# Power_Supply.net
KiCad netlist of a schematic drawn in Altium Designer
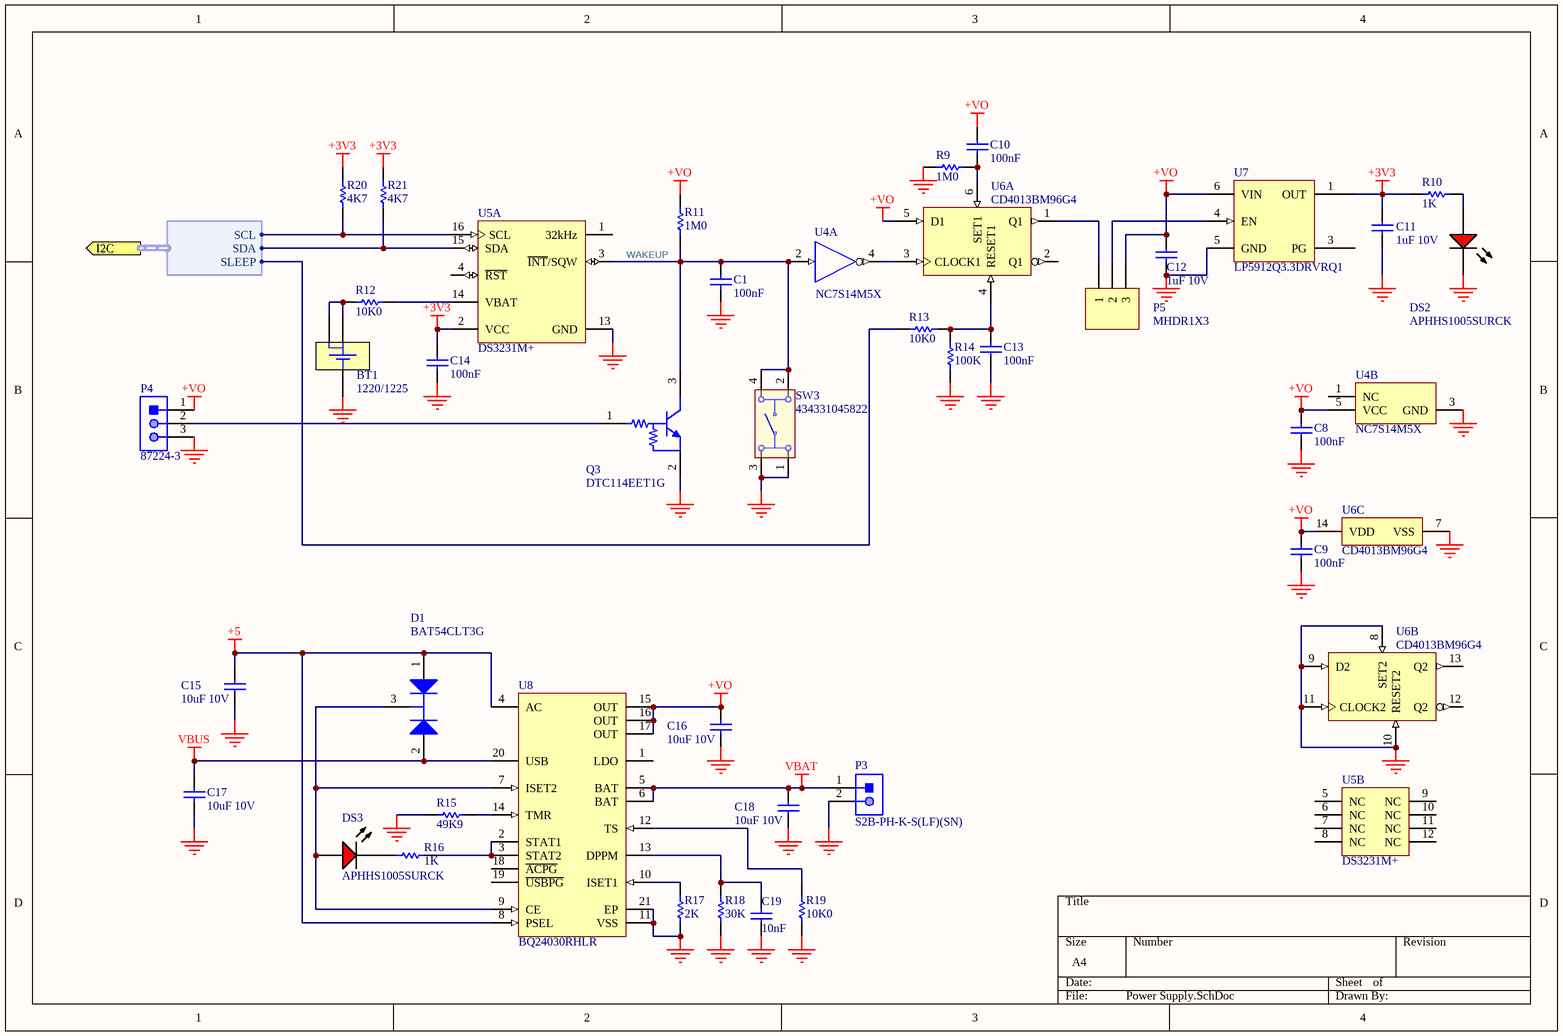
[diagram p0: Power Supply.SchDoc]

(export (version "E")
  (design (tool "Eeschema 10.0.6"))
  (components
    (comp (ref "BT1")
      (value "1220/1225")
      (footprint "KEYSTONE 3000")
      (description "Keystone 3000")
      (libsource (lib "Pathfinder") (part "3000"))
    )
    (comp (ref "C1")
      (value "100nF")
      (footprint "CAPC0402(1005)60_L")
      (description "CAP 100nF 50V ±10% 0402 (1005 Metric) Thickness 0.6mm SMD")
      (fields (field (name "TOLERANCE") "Â±10%"))
      (libsource (lib "Altium Content Vault") (part "CAP"))
    )
    (comp (ref "C8")
      (value "100nF")
      (footprint "CAPC0402(1005)60_L")
      (description "CAP 100nF 50V ±10% 0402 (1005 Metric) Thickness 0.6mm SMD")
      (fields (field (name "TOLERANCE") "Â±10%"))
      (libsource (lib "Altium Content Vault") (part "CAP"))
    )
    (comp (ref "C9")
      (value "100nF")
      (footprint "CAPC0402(1005)60_N")
      (description "CAP 100nF 50V ±10% 0402 (1005 Metric) Thickness 0.6mm SMD")
      (fields (field (name "TOLERANCE") "Â±10%"))
      (libsource (lib "Altium Content Vault") (part "CAP"))
    )
    (comp (ref "C10")
      (value "100nF")
      (footprint "CAPC0402(1005)60_L")
      (description "CAP 100nF 50V ±10% 0402 (1005 Metric) Thickness 0.6mm SMD")
      (fields (field (name "TOLERANCE") "Â±10%"))
      (libsource (lib "Altium Content Vault") (part "CAP"))
    )
    (comp (ref "C11")
      (value "1uF 10V")
      (footprint "CAPC0402(1005)60_L")
      (description "CAP 1uF 10V ±10% 0402 (1005 Metric) Thickness 0.6mm SMD")
      (fields (field (name "TOLERANCE") "Â±10%"))
      (libsource (lib "Altium Content Vault") (part "CAP"))
    )
    (comp (ref "C12")
      (value "1uF 10V")
      (footprint "CAPC0402(1005)60_L")
      (description "CAP 1uF 10V ±10% 0402 (1005 Metric) Thickness 0.6mm SMD")
      (fields (field (name "TOLERANCE") "Â±10%"))
      (libsource (lib "Altium Content Vault") (part "CAP"))
    )
    (comp (ref "C13")
      (value "100nF")
      (footprint "CAPC0402(1005)60_L")
      (description "CAP 100nF 50V ±10% 0402 (1005 Metric) Thickness 0.6mm SMD")
      (fields (field (name "TOLERANCE") "Â±10%"))
      (libsource (lib "Altium Content Vault") (part "CAP"))
    )
    (comp (ref "C14")
      (value "100nF")
      (footprint "CAPC0402(1005)60_L")
      (description "CAP 100nF 50V ±10% 0402 (1005 Metric) Thickness 0.6mm SMD")
      (fields (field (name "TOLERANCE") "Â±10%"))
      (libsource (lib "Altium Content Vault") (part "CAP"))
    )
    (comp (ref "C15")
      (value "10uF 10V")
      (footprint "CAPC0603(1608)100_L")
      (description "CAP 10uF 10V ±20% 0603 (1608 Metric) Thickness 1mm SMD")
      (fields (field (name "TOLERANCE") "Â±20%"))
      (libsource (lib "Altium Content Vault") (part "CAP"))
    )
    (comp (ref "C16")
      (value "10uF 10V")
      (footprint "CAPC0603(1608)100_L")
      (description "CAP 10uF 10V ±20% 0603 (1608 Metric) Thickness 1mm SMD")
      (fields (field (name "TOLERANCE") "Â±20%"))
      (libsource (lib "Altium Content Vault") (part "CAP"))
    )
    (comp (ref "C17")
      (value "10uF 10V")
      (footprint "CAPC0603(1608)100_L")
      (description "CAP 10uF 10V ±20% 0603 (1608 Metric) Thickness 1mm SMD")
      (fields (field (name "TOLERANCE") "Â±20%"))
      (libsource (lib "Altium Content Vault") (part "CAP"))
    )
    (comp (ref "C18")
      (value "10uF 10V")
      (footprint "CAPC0603(1608)100_L")
      (description "CAP 10uF 10V ±20% 0603 (1608 Metric) Thickness 1mm SMD")
      (fields (field (name "TOLERANCE") "Â±20%"))
      (libsource (lib "Altium Content Vault") (part "CAP"))
    )
    (comp (ref "C19")
      (value "10nF")
      (footprint "CAPC0402(1005)60_L")
      (description "CAP 10nF 50V ±10% 0402 (1005 Metric) Thickness 0.6mm SMD")
      (fields (field (name "TOLERANCE") "Â±10%"))
      (libsource (lib "Altium Content Vault") (part "CAP"))
    )
    (comp (ref "D1")
      (value "BAT54CLT3G")
      (footprint "ONSC-SOT-23-3-318-08_V")
      (description "Dual Common Cathode Schottky Barrier Diodes, 3-Pin SOT-23, Pb-Free, Tape and Reel")
      (fields (field (name "MANUFACTURER") "On Semiconductor"))
      (libsource (lib "Altium Content Vault") (part "ONSC-D-A1A2K3-3"))
    )
    (comp (ref "DS2")
      (value "APHHS1005SURCK")
      (footprint "KING-0402_V")
      (fields (field (name "MANUFACTURER") "Kingbright"))
      (libsource (lib "Altium Content Vault") (part "LED-RED-AK-2"))
    )
    (comp (ref "DS3")
      (value "APHHS1005SURCK")
      (footprint "KING-0402_V")
      (fields (field (name "MANUFACTURER") "Kingbright"))
      (libsource (lib "Altium Content Vault") (part "LED-RED-AK-2"))
    )
    (comp (ref "P3")
      (value "S2B-PH-K-S(LF)(SN)")
      (footprint "JST-S2B-PH-K-S_V")
      (fields (field (name "TOLERANCE") "20%"))
      (libsource (lib "Altium Content Vault") (part "CN-1P-M-R2"))
    )
    (comp (ref "P4")
      (value "87224-3")
      (footprint "TECO-87224-3_V")
      (fields (field (name "MANUFACTURER") "TE Connectivity"))
      (libsource (lib "Altium Content Vault") (part "CN-1P-M-R3"))
    )
    (comp (ref "P5")
      (value "MHDR1X3")
      (footprint "MHDR1X3")
      (description "Header, 3-Pin")
      (fields (field (name "PUBLISHER") "Altium Limited"))
      (libsource (lib "Miscellaneous Connectors") (part "MHDR1X3"))
    )
    (comp (ref "Q3")
      (value "DTC114EET1G")
      (footprint "ONSC-SC-75-3-463-01_V")
      (fields (field (name "MANUFACTURER") "On Semiconductor"))
      (libsource (lib "Altium Content Vault") (part "ONSC-BRT-NPN-B1E2C3-3"))
    )
    (comp (ref "R9")
      (value "1M0")
      (footprint "RESC0402(1005)_L")
      (description "1M 0.063W 1% 0402 (1005 Metric)  SMD")
      (fields (field (name "TOLERANCE") "1 %") (field (name "POWER") "0.063 W"))
      (libsource (lib "Altium Content Vault") (part "RES"))
    )
    (comp (ref "R10")
      (value "1K")
      (footprint "RESC0402(1005)_L")
      (description "1K 0.063W 1% 0402 (1005 Metric)  SMD")
      (fields (field (name "TOLERANCE") "1 %") (field (name "POWER") "0.063 W"))
      (libsource (lib "Altium Content Vault") (part "RES"))
    )
    (comp (ref "R11")
      (value "1M0")
      (footprint "RESC0402(1005)_L")
      (description "1M 0.063W 1% 0402 (1005 Metric)  SMD")
      (fields (field (name "TOLERANCE") "1 %") (field (name "POWER") "0.063 W"))
      (libsource (lib "Altium Content Vault") (part "RES"))
    )
    (comp (ref "R12")
      (value "10K0")
      (footprint "RESC0402(1005)_L")
      (description "10K 0.063W 1% 0402 (1005 Metric)  SMD")
      (fields (field (name "TOLERANCE") "1 %") (field (name "POWER") "0.063 W"))
      (libsource (lib "Altium Content Vault") (part "RES"))
    )
    (comp (ref "R13")
      (value "10K0")
      (footprint "RESC0402(1005)_L")
      (description "10K 0.063W 1% 0402 (1005 Metric)  SMD")
      (fields (field (name "TOLERANCE") "1 %") (field (name "POWER") "0.063 W"))
      (libsource (lib "Altium Content Vault") (part "RES"))
    )
    (comp (ref "R14")
      (value "100K")
      (footprint "RESC0402(1005)_L")
      (description "100K 0.063W 1% 0402 (1005 Metric)  SMD")
      (fields (field (name "POWER") "0.063 W") (field (name "TOLERANCE") "1 %"))
      (libsource (lib "Altium Content Vault") (part "RES"))
    )
    (comp (ref "R15")
      (value "49K9")
      (footprint "RESC0402(1005)_L")
      (description "49K9 0.063W 1% 0402 (1005 Metric)  SMD")
      (fields (field (name "POWER") "0.063 W") (field (name "TOLERANCE") "1 %"))
      (libsource (lib "Altium Content Vault") (part "RES"))
    )
    (comp (ref "R16")
      (value "1K")
      (footprint "RESC0402(1005)_L")
      (description "1K 0.063W 1% 0402 (1005 Metric)  SMD")
      (fields (field (name "TOLERANCE") "1 %") (field (name "POWER") "0.063 W"))
      (libsource (lib "Altium Content Vault") (part "RES"))
    )
    (comp (ref "R17")
      (value "2K")
      (footprint "RESC0402(1005)_L")
      (description "2K 0.063W 1% 0402 (1005 Metric)  SMD")
      (fields (field (name "POWER") "0.063 W") (field (name "TOLERANCE") "1 %"))
      (libsource (lib "Altium Content Vault") (part "RES"))
    )
    (comp (ref "R18")
      (value "30K")
      (footprint "RESC0402(1005)_L")
      (description "30K 0.063W 1% 0402 (1005 Metric)  SMD")
      (fields (field (name "POWER") "0.063 W") (field (name "TOLERANCE") "1 %"))
      (libsource (lib "Altium Content Vault") (part "RES"))
    )
    (comp (ref "R19")
      (value "10K0")
      (footprint "RESC0402(1005)_L")
      (description "10K 0.063W 1% 0402 (1005 Metric)  SMD")
      (fields (field (name "TOLERANCE") "1 %") (field (name "POWER") "0.063 W"))
      (libsource (lib "Altium Content Vault") (part "RES"))
    )
    (comp (ref "R20")
      (value "4K7")
      (footprint "RESC0402(1005)_L")
      (description "4K7 0.063W 1% 0402 (1005 Metric)  SMD")
      (fields (field (name "POWER") "0.063 W") (field (name "TOLERANCE") "1 %"))
      (libsource (lib "Altium Content Vault") (part "RES"))
    )
    (comp (ref "R21")
      (value "4K7")
      (footprint "RESC0402(1005)_L")
      (description "4K7 0.063W 1% 0402 (1005 Metric)  SMD")
      (fields (field (name "POWER") "0.063 W") (field (name "TOLERANCE") "1 %"))
      (libsource (lib "Altium Content Vault") (part "RES"))
    )
    (comp (ref "SW3")
      (value "434331045822")
      (footprint "434331045822")
      (description "WS-TASU SMD Tact Switch 4.7X3.5 mm side push")
      (fields (field (name "MANUFACTURER") "Wuerth Elektronik"))
      (libsource (lib "Altium Content Vault") (part "WE-TACT-SW-4"))
    )
    (comp (ref "U4")
      (value "NC7S14M5X")
      (footprint "FAIR-SOT23-5_V")
      (fields (field (name "MANUFACTURER") "Fairchild Semiconductor"))
      (libsource (lib "Altium Content Vault") (part "FAIR-NC7S14-SOT23-5"))
    )
    (comp (ref "U5")
      (value "DS3231M+")
      (footprint "W16MK+1_M")
      (description "+/-5ppm, MEMS based Real-Time Clock, I2C Interface, 16-Pin SO, -40 to 85 degC, Pb-Free")
      (libsource (lib "Altium Content Vault") (part "PR-RTC-DS3231M-IL16"))
    )
    (comp (ref "U6")
      (value "CD4013BM96G4")
      (footprint "D0014A_L")
      (description "CMOS Dual D-Type Flip Flop, D0014A, LARGE T&R")
      (fields
        (field (name "MANUFACTURER") "Texas Instruments")
        (field (name "GENERIC PART NUMBER") "CD4013B")
      )
      (libsource (lib "") (part "TI-CD4013B-14_1"))
    )
    (comp (ref "U7")
      (value "LP5912Q3.3DRVRQ1")
      (footprint "WSON65P200X80_HS-7N")
      (description "Linear Voltage Regulator IC 1 Output 500mA 6-WSON (2x2)")
      (libsource (lib "Pathfinder") (part "LP5912Q3.3DRVRQ1"))
    )
    (comp (ref "U8")
      (value "BQ24030RHLR")
      (footprint "RHL0020A_V")
      (fields (field (name "MANUFACTURER") "Texas Instruments"))
      (libsource (lib "Altium Content Vault") (part "TI-BQ24030RHL20-3050X2050TP"))
    )
  )
  (nets
    (net (code "2") (name "+3V3") (class "Default")
      (node (ref "C11") (pin "1") (pinfunction "1_1") (pintype "passive"))
      (node (ref "C14") (pin "2") (pinfunction "2_2") (pintype "passive"))
      (node (ref "R10") (pin "1") (pinfunction "1_1") (pintype "passive"))
      (node (ref "R20") (pin "2") (pinfunction "2_2") (pintype "passive"))
      (node (ref "R21") (pin "2") (pinfunction "2_2") (pintype "passive"))
      (node (ref "U5") (pin "2") (pinfunction "VCC_2") (pintype "power_in"))
      (node (ref "U7") (pin "1") (pinfunction "OUT_1") (pintype "power_in"))
    )
    (net (code "3") (name "+5") (class "Default")
      (node (ref "C15") (pin "1") (pinfunction "1_1") (pintype "passive"))
      (node (ref "D1") (pin "1") (pinfunction "A1_1") (pintype "passive"))
      (node (ref "U8") (pin "4") (pinfunction "AC_4") (pintype "power_in"))
      (node (ref "U8") (pin "8") (pinfunction "PSEL_8") (pintype "input"))
    )
    (net (code "4") (name "+VO") (class "Default")
      (node (ref "C10") (pin "2") (pinfunction "2_2") (pintype "passive"))
      (node (ref "C12") (pin "1") (pinfunction "1_1") (pintype "passive"))
      (node (ref "C16") (pin "1") (pinfunction "1_1") (pintype "passive"))
      (node (ref "C8") (pin "2") (pinfunction "2_2") (pintype "passive"))
      (node (ref "C9") (pin "2") (pinfunction "2_2") (pintype "passive"))
      (node (ref "P4") (pin "1") (pinfunction "1_1") (pintype "passive"))
      (node (ref "P5") (pin "3") (pinfunction "3_3") (pintype "passive"))
      (node (ref "R11") (pin "2") (pinfunction "2_2") (pintype "passive"))
      (node (ref "U4") (pin "5") (pinfunction "VCC_5") (pintype "power_in"))
      (node (ref "U6") (pin "14") (pinfunction "VDD_14") (pintype "power_in"))
      (node (ref "U6") (pin "5") (pinfunction "D1_5") (pintype "input"))
      (node (ref "U7") (pin "6") (pinfunction "VIN_6") (pintype "power_in"))
      (node (ref "U8") (pin "15") (pinfunction "OUT_15") (pintype "power_in"))
      (node (ref "U8") (pin "16") (pinfunction "OUT_16") (pintype "power_in"))
      (node (ref "U8") (pin "17") (pinfunction "OUT_17") (pintype "power_in"))
    )
    (net (code "5") (name "/SCL") (class "Default")
      (node (ref "R20") (pin "1") (pinfunction "1_1") (pintype "passive"))
      (node (ref "U5") (pin "16") (pinfunction "SCL_16") (pintype "input"))
    )
    (net (code "6") (name "/SDA") (class "Default")
      (node (ref "R21") (pin "1") (pinfunction "1_1") (pintype "passive"))
      (node (ref "U5") (pin "15") (pinfunction "SDA_15") (pintype "bidirectional"))
    )
    (net (code "7") (name "/SLEEP") (class "Default")
      (node (ref "R13") (pin "1") (pinfunction "1_1") (pintype "passive"))
    )
    (net (code "8") (name "/WAKEUP") (class "Default")
      (node (ref "C1") (pin "2") (pinfunction "2_2") (pintype "passive"))
      (node (ref "Q3") (pin "3") (pinfunction "C_3") (pintype "passive"))
      (node (ref "R11") (pin "1") (pinfunction "1_1") (pintype "passive"))
      (node (ref "SW3") (pin "2") (pinfunction "2_2") (pintype "passive"))
      (node (ref "SW3") (pin "4") (pinfunction "4_4") (pintype "passive"))
      (node (ref "U4") (pin "2") (pinfunction "A_2") (pintype "input"))
      (node (ref "U5") (pin "3") (pinfunction "~{INT}/SQW_3") (pintype "bidirectional"))
    )
    (net (code "10") (name "GND") (class "Default")
      (node (ref "BT1") (pin "2") (pinfunction "-_2") (pintype "passive"))
      (node (ref "C1") (pin "1") (pinfunction "1_1") (pintype "passive"))
      (node (ref "C11") (pin "2") (pinfunction "2_2") (pintype "passive"))
      (node (ref "C12") (pin "2") (pinfunction "2_2") (pintype "passive"))
      (node (ref "C13") (pin "1") (pinfunction "1_1") (pintype "passive"))
      (node (ref "C14") (pin "1") (pinfunction "1_1") (pintype "passive"))
      (node (ref "C15") (pin "2") (pinfunction "2_2") (pintype "passive"))
      (node (ref "C16") (pin "2") (pinfunction "2_2") (pintype "passive"))
      (node (ref "C17") (pin "2") (pinfunction "2_2") (pintype "passive"))
      (node (ref "C18") (pin "2") (pinfunction "2_2") (pintype "passive"))
      (node (ref "C19") (pin "1") (pinfunction "1_1") (pintype "passive"))
      (node (ref "C8") (pin "1") (pinfunction "1_1") (pintype "passive"))
      (node (ref "C9") (pin "1") (pinfunction "1_1") (pintype "passive"))
      (node (ref "DS2") (pin "2") (pinfunction "K_2") (pintype "passive"))
      (node (ref "P3") (pin "2") (pinfunction "2_2") (pintype "passive"))
      (node (ref "P4") (pin "3") (pinfunction "3_3") (pintype "passive"))
      (node (ref "Q3") (pin "2") (pinfunction "E_2") (pintype "passive"))
      (node (ref "R14") (pin "1") (pinfunction "1_1") (pintype "passive"))
      (node (ref "R15") (pin "1") (pinfunction "1_1") (pintype "passive"))
      (node (ref "R17") (pin "1") (pinfunction "1_1") (pintype "passive"))
      (node (ref "R18") (pin "1") (pinfunction "1_1") (pintype "passive"))
      (node (ref "R19") (pin "1") (pinfunction "1_1") (pintype "passive"))
      (node (ref "R9") (pin "2") (pinfunction "2_2") (pintype "passive"))
      (node (ref "SW3") (pin "1") (pinfunction "1_1") (pintype "passive"))
      (node (ref "SW3") (pin "3") (pinfunction "3_3") (pintype "passive"))
      (node (ref "U4") (pin "3") (pinfunction "GND_3") (pintype "power_in"))
      (node (ref "U5") (pin "13") (pinfunction "GND_13") (pintype "power_in"))
      (node (ref "U6") (pin "10") (pinfunction "RESET2_10") (pintype "input"))
      (node (ref "U6") (pin "11") (pinfunction "CLOCK2_11") (pintype "input"))
      (node (ref "U6") (pin "7") (pinfunction "VSS_7") (pintype "power_in"))
      (node (ref "U6") (pin "8") (pinfunction "SET2_8") (pintype "input"))
      (node (ref "U6") (pin "9") (pinfunction "D2_9") (pintype "input"))
      (node (ref "U7") (pin "5") (pinfunction "GND_5") (pintype "power_in"))
      (node (ref "U8") (pin "11") (pinfunction "VSS_11") (pintype "power_in"))
      (node (ref "U8") (pin "21") (pinfunction "EP_21") (pintype "power_in"))
    )
    (net (code "11") (name "Net-(BT1-+-Pad1)") (class "Default")
      (node (ref "BT1") (pin "1") (pinfunction "+_1") (pintype "passive"))
      (node (ref "BT1") (pin "3") (pinfunction "+_3") (pintype "passive"))
      (node (ref "R12") (pin "2") (pinfunction "2_2") (pintype "passive"))
    )
    (net (code "12") (name "Net-(D1-K)") (class "Default")
      (node (ref "D1") (pin "3") (pinfunction "K_3") (pintype "passive"))
      (node (ref "DS3") (pin "1") (pinfunction "A_1") (pintype "passive"))
      (node (ref "U8") (pin "7") (pinfunction "ISET2_7") (pintype "input"))
      (node (ref "U8") (pin "9") (pinfunction "CE_9") (pintype "input"))
    )
    (net (code "13") (name "Net-(DS2-A)") (class "Default")
      (node (ref "DS2") (pin "1") (pinfunction "A_1") (pintype "passive"))
      (node (ref "R10") (pin "2") (pinfunction "2_2") (pintype "passive"))
    )
    (net (code "14") (name "Net-(DS3-K)") (class "Default")
      (node (ref "DS3") (pin "2") (pinfunction "K_2") (pintype "passive"))
      (node (ref "R16") (pin "1") (pinfunction "1_1") (pintype "passive"))
    )
    (net (code "15") (name "Net-(P5-Pad1)") (class "Default")
      (node (ref "P5") (pin "1") (pinfunction "1_1") (pintype "passive"))
      (node (ref "U6") (pin "1") (pinfunction "Q1_1") (pintype "output"))
    )
    (net (code "16") (name "Net-(Q3-B)") (class "Default")
      (node (ref "P4") (pin "2") (pinfunction "2_2") (pintype "passive"))
      (node (ref "Q3") (pin "1") (pinfunction "B_1") (pintype "passive"))
    )
    (net (code "17") (name "Net-(U4A-Y)") (class "Default")
      (node (ref "U4") (pin "4") (pinfunction "Y_4") (pintype "output"))
      (node (ref "U6") (pin "3") (pinfunction "CLOCK1_3") (pintype "input"))
    )
    (net (code "18") (name "Net-(U5A-VBAT)") (class "Default")
      (node (ref "R12") (pin "1") (pinfunction "1_1") (pintype "passive"))
      (node (ref "U5") (pin "14") (pinfunction "VBAT_14") (pintype "power_in"))
    )
    (net (code "19") (name "Net-(U6A-RESET1)") (class "Default")
      (node (ref "C13") (pin "2") (pinfunction "2_2") (pintype "passive"))
      (node (ref "R13") (pin "2") (pinfunction "2_2") (pintype "passive"))
      (node (ref "R14") (pin "2") (pinfunction "2_2") (pintype "passive"))
      (node (ref "U6") (pin "4") (pinfunction "RESET1_4") (pintype "input"))
    )
    (net (code "20") (name "Net-(U6A-SET1)") (class "Default")
      (node (ref "C10") (pin "1") (pinfunction "1_1") (pintype "passive"))
      (node (ref "R9") (pin "1") (pinfunction "1_1") (pintype "passive"))
      (node (ref "U6") (pin "6") (pinfunction "SET1_6") (pintype "input"))
    )
    (net (code "21") (name "Net-(U7-EN)") (class "Default")
      (node (ref "P5") (pin "2") (pinfunction "2_2") (pintype "passive"))
      (node (ref "U7") (pin "4") (pinfunction "EN_4") (pintype "input"))
    )
    (net (code "22") (name "Net-(U8-DPPM)") (class "Default")
      (node (ref "C19") (pin "2") (pinfunction "2_2") (pintype "passive"))
      (node (ref "R18") (pin "2") (pinfunction "2_2") (pintype "passive"))
      (node (ref "U8") (pin "13") (pinfunction "DPPM_13") (pintype "passive"))
    )
    (net (code "23") (name "Net-(U8-ISET1)") (class "Default")
      (node (ref "R17") (pin "2") (pinfunction "2_2") (pintype "passive"))
      (node (ref "U8") (pin "10") (pinfunction "ISET1_10") (pintype "input"))
    )
    (net (code "24") (name "Net-(U8-STAT1)") (class "Default")
      (node (ref "R16") (pin "2") (pinfunction "2_2") (pintype "passive"))
      (node (ref "U8") (pin "2") (pinfunction "STAT1_2") (pintype "open_collector"))
      (node (ref "U8") (pin "3") (pinfunction "STAT2_3") (pintype "open_collector"))
    )
    (net (code "25") (name "Net-(U8-TMR)") (class "Default")
      (node (ref "R15") (pin "2") (pinfunction "2_2") (pintype "passive"))
      (node (ref "U8") (pin "14") (pinfunction "TMR_14") (pintype "input"))
    )
    (net (code "26") (name "Net-(U8-TS)") (class "Default")
      (node (ref "R19") (pin "2") (pinfunction "2_2") (pintype "passive"))
      (node (ref "U8") (pin "12") (pinfunction "TS_12") (pintype "input"))
    )
    (net (code "27") (name "VBAT") (class "Default")
      (node (ref "C18") (pin "1") (pinfunction "1_1") (pintype "passive"))
      (node (ref "P3") (pin "1") (pinfunction "1_1") (pintype "passive"))
      (node (ref "U8") (pin "5") (pinfunction "BAT_5") (pintype "power_in"))
      (node (ref "U8") (pin "6") (pinfunction "BAT_6") (pintype "power_in"))
    )
    (net (code "28") (name "VBUS") (class "Default")
      (node (ref "C17") (pin "1") (pinfunction "1_1") (pintype "passive"))
      (node (ref "D1") (pin "2") (pinfunction "A2_2") (pintype "passive"))
      (node (ref "U8") (pin "20") (pinfunction "USB_20") (pintype "power_in"))
    )
    (net (code "29") (name "unconnected-(U4B-NC-Pad1)") (class "Default")
      (node (ref "U4") (pin "1") (pinfunction "NC_1") (pintype "power_in"))
    )
    (net (code "30") (name "unconnected-(U5A-32kHz-Pad1)") (class "Default")
      (node (ref "U5") (pin "1") (pinfunction "32kHz_1") (pintype "open_collector"))
    )
    (net (code "31") (name "unconnected-(U5A-~{RST}-Pad4)") (class "Default")
      (node (ref "U5") (pin "4") (pinfunction "~{RST}_4") (pintype "bidirectional"))
    )
    (net (code "32") (name "unconnected-(U5B-NC-Pad5)") (class "Default")
      (node (ref "U5") (pin "5") (pinfunction "NC_5") (pintype "passive"))
    )
    (net (code "33") (name "unconnected-(U5B-NC-Pad6)") (class "Default")
      (node (ref "U5") (pin "6") (pinfunction "NC_6") (pintype "passive"))
    )
    (net (code "34") (name "unconnected-(U5B-NC-Pad7)") (class "Default")
      (node (ref "U5") (pin "7") (pinfunction "NC_7") (pintype "passive"))
    )
    (net (code "35") (name "unconnected-(U5B-NC-Pad8)") (class "Default")
      (node (ref "U5") (pin "8") (pinfunction "NC_8") (pintype "passive"))
    )
    (net (code "36") (name "unconnected-(U5B-NC-Pad9)") (class "Default")
      (node (ref "U5") (pin "9") (pinfunction "NC_9") (pintype "passive"))
    )
    (net (code "37") (name "unconnected-(U5B-NC-Pad10)") (class "Default")
      (node (ref "U5") (pin "10") (pinfunction "NC_10") (pintype "passive"))
    )
    (net (code "38") (name "unconnected-(U5B-NC-Pad11)") (class "Default")
      (node (ref "U5") (pin "11") (pinfunction "NC_11") (pintype "passive"))
    )
    (net (code "39") (name "unconnected-(U5B-NC-Pad12)") (class "Default")
      (node (ref "U5") (pin "12") (pinfunction "NC_12") (pintype "passive"))
    )
    (net (code "40") (name "unconnected-(U6A-Q1-Pad2)") (class "Default")
      (node (ref "U6") (pin "2") (pinfunction "Q1_2") (pintype "output"))
    )
    (net (code "41") (name "unconnected-(U6B-Q2-Pad12)") (class "Default")
      (node (ref "U6") (pin "12") (pinfunction "Q2_12") (pintype "output"))
    )
    (net (code "42") (name "unconnected-(U6B-Q2-Pad13)") (class "Default")
      (node (ref "U6") (pin "13") (pinfunction "Q2_13") (pintype "output"))
    )
    (net (code "43") (name "unconnected-(U7-PG-Pad3)") (class "Default")
      (node (ref "U7") (pin "3") (pinfunction "PG_3") (pintype "open_collector"))
    )
    (net (code "44") (name "unconnected-(U8-LDO-Pad1)") (class "Default")
      (node (ref "U8") (pin "1") (pinfunction "LDO_1") (pintype "power_in"))
    )
    (net (code "45") (name "unconnected-(U8-~{ACPG}-Pad18)") (class "Default")
      (node (ref "U8") (pin "18") (pinfunction "~{ACPG}_18") (pintype "open_collector"))
    )
    (net (code "46") (name "unconnected-(U8-~{USBPG}-Pad19)") (class "Default")
      (node (ref "U8") (pin "19") (pinfunction "~{USBPG}_19") (pintype "open_collector"))
    )
  )
)
